# sch.net
KiCad netlist of a schematic drawn in Altium Designer
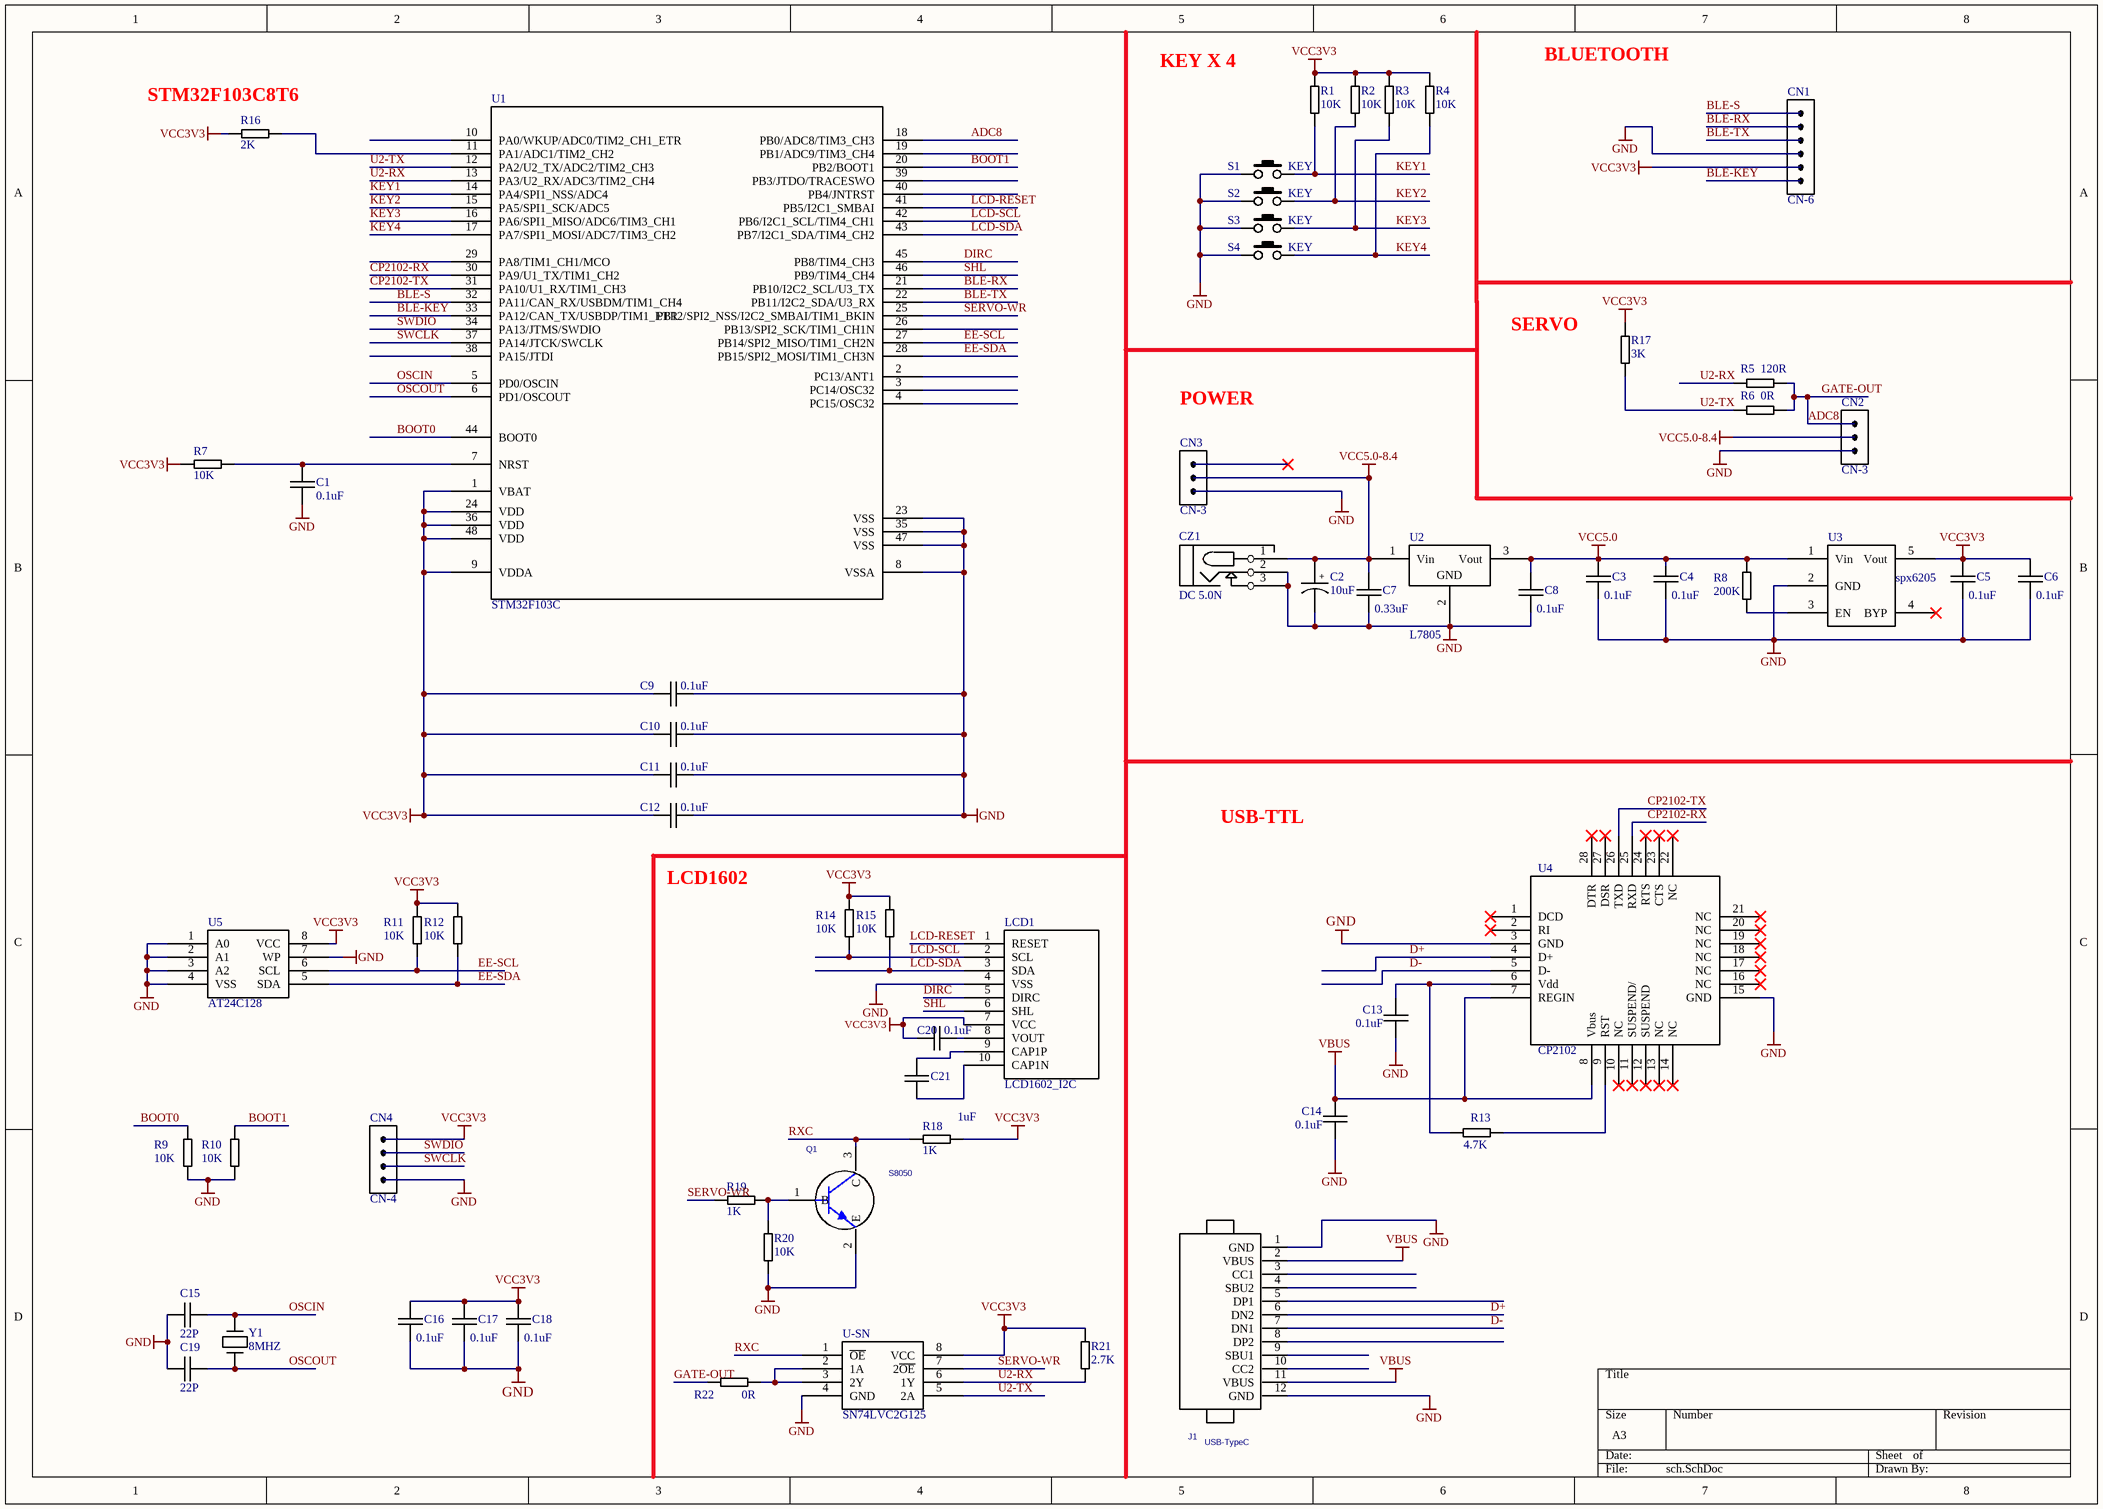
[diagram p0: sch.SchDoc]

(export (version "E")
  (design (tool "Eeschema 10.0.6"))
  (components
    (comp (ref "C1")
      (value "0.1uF")
      (footprint "CAP-0603")
      (description "Capacitor")
      (libsource (lib "综合元件") (part "CAP"))
    )
    (comp (ref "C2")
      (value "10uF")
      (footprint "CAP-A")
      (description "Polar Capacitor")
      (libsource (lib "1-Components") (part "CAP(POL)"))
    )
    (comp (ref "C3")
      (value "0.1uF")
      (footprint "CAP-0603")
      (description "Capacitor")
      (libsource (lib "综合元件") (part "CAP"))
    )
    (comp (ref "C4")
      (value "0.1uF")
      (footprint "CAP-0603")
      (description "Capacitor")
      (libsource (lib "综合元件") (part "CAP"))
    )
    (comp (ref "C5")
      (value "0.1uF")
      (footprint "CAP-0603")
      (description "Capacitor")
      (libsource (lib "综合元件") (part "CAP"))
    )
    (comp (ref "C6")
      (value "0.1uF")
      (footprint "CAP-0603")
      (description "Capacitor")
      (libsource (lib "综合元件") (part "CAP"))
    )
    (comp (ref "C7")
      (value "0.33uF")
      (footprint "CAP-0603")
      (description "Capacitor")
      (libsource (lib "综合元件") (part "CAP"))
    )
    (comp (ref "C8")
      (value "0.1uF")
      (footprint "CAP-0603")
      (description "Capacitor")
      (libsource (lib "综合元件") (part "CAP"))
    )
    (comp (ref "C9")
      (value "0.1uF")
      (footprint "CAP-0603")
      (description "Capacitor")
      (libsource (lib "综合元件") (part "CAP"))
    )
    (comp (ref "C10")
      (value "0.1uF")
      (footprint "CAP-0603")
      (description "Capacitor")
      (libsource (lib "综合元件") (part "CAP"))
    )
    (comp (ref "C11")
      (value "0.1uF")
      (footprint "CAP-0603")
      (description "Capacitor")
      (libsource (lib "综合元件") (part "CAP"))
    )
    (comp (ref "C12")
      (value "0.1uF")
      (footprint "CAP-0603")
      (description "Capacitor")
      (libsource (lib "综合元件") (part "CAP"))
    )
    (comp (ref "C13")
      (value "0.1uF")
      (footprint "CAP-0603")
      (description "Capacitor")
      (libsource (lib "综合元件") (part "CAP"))
    )
    (comp (ref "C14")
      (value "0.1uF")
      (footprint "CAP-0603")
      (description "Capacitor")
      (libsource (lib "综合元件") (part "CAP"))
    )
    (comp (ref "C15")
      (value "22P")
      (footprint "CAP-0603")
      (description "Capacitor")
      (libsource (lib "1-Components") (part "CAP"))
    )
    (comp (ref "C16")
      (value "0.1uF")
      (footprint "CAP-0603")
      (description "Capacitor")
      (libsource (lib "综合元件") (part "CAP"))
    )
    (comp (ref "C17")
      (value "0.1uF")
      (footprint "CAP-0603")
      (description "Capacitor")
      (libsource (lib "综合元件") (part "CAP"))
    )
    (comp (ref "C18")
      (value "0.1uF")
      (footprint "CAP-0603")
      (description "Capacitor")
      (libsource (lib "综合元件") (part "CAP"))
    )
    (comp (ref "C19")
      (value "22P")
      (footprint "CAP-0603")
      (description "Capacitor")
      (libsource (lib "1-Components") (part "CAP"))
    )
    (comp (ref "C20")
      (value "0.1uF")
      (footprint "CAP-0603")
      (description "Capacitor")
      (libsource (lib "综合元件") (part "CAP"))
    )
    (comp (ref "C21")
      (value "1uF")
      (footprint "CAP-0603")
      (description "Capacitor")
      (libsource (lib "综合元件") (part "CAP"))
    )
    (comp (ref "CN1") (value "CN-6") (footprint "CN-6") (libsource (lib "2-Connectors") (part "CN-6")))
    (comp (ref "CN2") (value "CN-3") (footprint "IDC-3×1") (libsource (lib "2-Connectors") (part "CN-3")))
    (comp (ref "CN3") (value "CN-3") (footprint "IDC-3×1") (libsource (lib "2-Connectors") (part "CN-3")))
    (comp (ref "CN4") (value "CN-4") (footprint "IDC-4×1") (libsource (lib "2-Connectors") (part "CN-4")))
    (comp (ref "CZ1")
      (value "DC 5.0N")
      (footprint "DC-005(N)")
      (libsource (lib "2-Connectors") (part "DC 5.0N"))
    )
    (comp (ref "J1")
      (value "USB-TypeC")
      (footprint "USB-TYPEC")
      (libsource (lib "2-Connectors") (part "USB-TypeC"))
    )
    (comp (ref "LCD1")
      (value "LCD1602_I2C")
      (footprint "LCD-IIC")
      (description "LCD1602")
      (libsource (lib "6-Modulars") (part "LCD1602_I2C"))
    )
    (comp (ref "Q1")
      (value "S8050")
      (footprint "SOT-23(3)")
      (description "NPN")
      (libsource (lib "3-ICs Normal") (part "S8050"))
    )
    (comp (ref "R1")
      (value "10K")
      (footprint "RES-0603")
      (description "Resistor")
      (libsource (lib "1-Components") (part "RES"))
    )
    (comp (ref "R2")
      (value "10K")
      (footprint "RES-0603")
      (description "Resistor")
      (libsource (lib "1-Components") (part "RES"))
    )
    (comp (ref "R3")
      (value "10K")
      (footprint "RES-0603")
      (description "Resistor")
      (libsource (lib "1-Components") (part "RES"))
    )
    (comp (ref "R4")
      (value "10K")
      (footprint "RES-0603")
      (description "Resistor")
      (libsource (lib "1-Components") (part "RES"))
    )
    (comp (ref "R5")
      (value "120R")
      (footprint "RES-0603")
      (description "Resistor")
      (libsource (lib "1-Components") (part "RES"))
    )
    (comp (ref "R6")
      (value "0R")
      (footprint "RES-0603")
      (description "Resistor")
      (libsource (lib "1-Components") (part "RES"))
    )
    (comp (ref "R7")
      (value "10K")
      (footprint "RES-0603")
      (description "Resistor")
      (libsource (lib "综合元件") (part "RES"))
    )
    (comp (ref "R8")
      (value "200K")
      (footprint "RES-0603")
      (description "Resistor")
      (libsource (lib "1-Components") (part "RES"))
    )
    (comp (ref "R9")
      (value "10K")
      (footprint "RES-0603")
      (description "Resistor")
      (libsource (lib "1-Components") (part "RES"))
    )
    (comp (ref "R10")
      (value "10K")
      (footprint "RES-0603")
      (description "Resistor")
      (libsource (lib "1-Components") (part "RES"))
    )
    (comp (ref "R11")
      (value "10K")
      (footprint "RES-0603")
      (description "Resistor")
      (libsource (lib "1-Components") (part "RES"))
    )
    (comp (ref "R12")
      (value "10K")
      (footprint "RES-0603")
      (description "Resistor")
      (libsource (lib "1-Components") (part "RES"))
    )
    (comp (ref "R13")
      (value "4.7K")
      (footprint "RES-0603")
      (description "Resistor")
      (libsource (lib "1-Components") (part "RES"))
    )
    (comp (ref "R14")
      (value "10K")
      (footprint "RES-0603")
      (description "Resistor")
      (libsource (lib "1-Components") (part "RES"))
    )
    (comp (ref "R15")
      (value "10K")
      (footprint "RES-0603")
      (description "Resistor")
      (libsource (lib "1-Components") (part "RES"))
    )
    (comp (ref "R16")
      (value "2K")
      (footprint "RES-0603")
      (description "Resistor")
      (libsource (lib "1-Components") (part "RES"))
    )
    (comp (ref "R17")
      (value "3K")
      (footprint "RES-0603")
      (description "Resistor")
      (libsource (lib "1-Components") (part "RES"))
    )
    (comp (ref "R18")
      (value "1K")
      (footprint "RES-0603")
      (description "Resistor")
      (libsource (lib "1-Components") (part "RES"))
    )
    (comp (ref "R19")
      (value "1K")
      (footprint "RES-0603")
      (description "Resistor")
      (libsource (lib "1-Components") (part "RES"))
    )
    (comp (ref "R20")
      (value "10K")
      (footprint "RES-0603")
      (description "Resistor")
      (libsource (lib "1-Components") (part "RES"))
    )
    (comp (ref "R21")
      (value "2.7K")
      (footprint "RES-0603")
      (description "Resistor")
      (libsource (lib "1-Components") (part "RES"))
    )
    (comp (ref "R22")
      (value "0R")
      (footprint "RES-0603")
      (description "Resistor")
      (libsource (lib "1-Components") (part "RES"))
    )
    (comp (ref "S1") (value "KEY") (footprint "KEY-4X4X1.5") (libsource (lib "2-Connectors") (part "KEY")))
    (comp (ref "S2") (value "KEY") (footprint "KEY-4X4X1.5") (libsource (lib "2-Connectors") (part "KEY")))
    (comp (ref "S3") (value "KEY") (footprint "KEY-4X4X1.5") (libsource (lib "2-Connectors") (part "KEY")))
    (comp (ref "S4") (value "KEY") (footprint "KEY-4X4X1.5") (libsource (lib "2-Connectors") (part "KEY")))
    (comp (ref "U-SN")
      (value "SN74LVC2G125")
      (footprint "SOP-8(SN74)")
      (libsource (lib "3-ICs Normal") (part "SN74LVC2G125"))
    )
    (comp (ref "U1")
      (value "STM32F103C")
      (footprint "LQFP-48")
      (fields (field (name "PUBLISHER") "Altium Limited"))
      (libsource (lib "5-ICs Mcu") (part "STM32F103C(LQFP)"))
    )
    (comp (ref "U2") (value "L7805") (footprint "TO-252") (libsource (lib "3-ICs Normal") (part "78XX")))
    (comp (ref "U3")
      (value "spx6205")
      (footprint "SOT-23(5)")
      (libsource (lib "3-ICs Normal") (part "SP6205(FIXED)"))
    )
    (comp (ref "U4") (value "CP2102") (footprint "QFN-28") (libsource (lib "5-ICs Mcu") (part "MPU6050_1")))
    (comp (ref "U5")
      (value "AT24C128")
      (footprint "SOP-8(3.9)")
      (libsource (lib "3-ICs Normal") (part "AT24C128"))
    )
    (comp (ref "Y1")
      (value "8MHZ")
      (footprint "XTAL-2512")
      (description "Crystal")
      (libsource (lib "1-Components") (part "XTAL(1)"))
    )
  )
  (nets
    (net (code "1") (name "/ADC8") (class "Default")
      (node (ref "CN2") (pin "1") (pinfunction "1_1") (pintype "passive"))
      (node (ref "R22") (pin "2") (pinfunction "2_2") (pintype "passive"))
      (node (ref "R5") (pin "2") (pinfunction "2_2") (pintype "passive"))
      (node (ref "R6") (pin "2") (pinfunction "2_2") (pintype "passive"))
      (node (ref "U1") (pin "18") (pinfunction "PB0/ADC8/TIM3_CH3_18") (pintype "passive"))
    )
    (net (code "2") (name "/BLE-KEY") (class "Default")
      (node (ref "CN1") (pin "6") (pinfunction "6_6") (pintype "passive"))
      (node (ref "U1") (pin "33") (pinfunction "PA12/CAN_TX/USBDP/TIM1_ETR_33") (pintype "passive"))
    )
    (net (code "3") (name "/BLE-RX") (class "Default")
      (node (ref "CN1") (pin "2") (pinfunction "2_2") (pintype "passive"))
      (node (ref "U1") (pin "21") (pinfunction "PB10/I2C2_SCL/U3_TX_21") (pintype "passive"))
    )
    (net (code "4") (name "/BLE-S") (class "Default")
      (node (ref "CN1") (pin "1") (pinfunction "1_1") (pintype "passive"))
      (node (ref "U1") (pin "32") (pinfunction "PA11/CAN_RX/USBDM/TIM1_CH4_32") (pintype "passive"))
    )
    (net (code "5") (name "/BLE-TX") (class "Default")
      (node (ref "CN1") (pin "3") (pinfunction "3_3") (pintype "passive"))
      (node (ref "U1") (pin "22") (pinfunction "PB11/I2C2_SDA/U3_RX_22") (pintype "passive"))
    )
    (net (code "6") (name "/BOOT0") (class "Default")
      (node (ref "R9") (pin "1") (pinfunction "1_1") (pintype "passive"))
      (node (ref "U1") (pin "44") (pinfunction "BOOT0_44") (pintype "passive"))
    )
    (net (code "7") (name "/BOOT1") (class "Default")
      (node (ref "R10") (pin "1") (pinfunction "1_1") (pintype "passive"))
      (node (ref "U1") (pin "20") (pinfunction "PB2/BOOT1_20") (pintype "passive"))
    )
    (net (code "8") (name "/CP2102-RX") (class "Default")
      (node (ref "U1") (pin "30") (pinfunction "PA9/U1_TX/TIM1_CH2_30") (pintype "passive"))
      (node (ref "U4") (pin "25") (pinfunction "RXD_25") (pintype "passive"))
    )
    (net (code "9") (name "/CP2102-TX") (class "Default")
      (node (ref "U1") (pin "31") (pinfunction "PA10/U1_RX/TIM1_CH3_31") (pintype "passive"))
      (node (ref "U4") (pin "26") (pinfunction "TXD_26") (pintype "passive"))
    )
    (net (code "10") (name "/D+") (class "Default")
      (node (ref "J1") (pin "6") (pinfunction "DN2_6") (pintype "passive"))
      (node (ref "U4") (pin "4") (pinfunction "D+_4") (pintype "passive"))
    )
    (net (code "11") (name "/D-") (class "Default")
      (node (ref "J1") (pin "7") (pinfunction "DN1_7") (pintype "passive"))
      (node (ref "U4") (pin "5") (pinfunction "D-_5") (pintype "passive"))
    )
    (net (code "12") (name "/DIRC") (class "Default")
      (node (ref "LCD1") (pin "5") (pinfunction "DIRC_5") (pintype "passive"))
      (node (ref "U1") (pin "45") (pinfunction "PB8/TIM4_CH3_45") (pintype "passive"))
    )
    (net (code "13") (name "/EE-SCL") (class "Default")
      (node (ref "R11") (pin "2") (pinfunction "2_2") (pintype "passive"))
      (node (ref "U1") (pin "27") (pinfunction "PB14/SPI2_MISO/TIM1_CH2N_27") (pintype "passive"))
      (node (ref "U5") (pin "6") (pinfunction "SCL_6") (pintype "passive"))
    )
    (net (code "14") (name "/EE-SDA") (class "Default")
      (node (ref "R12") (pin "2") (pinfunction "2_2") (pintype "passive"))
      (node (ref "U1") (pin "28") (pinfunction "PB15/SPI2_MOSI/TIM1_CH3N_28") (pintype "passive"))
      (node (ref "U5") (pin "5") (pinfunction "SDA_5") (pintype "passive"))
    )
    (net (code "15") (name "/KEY1") (class "Default")
      (node (ref "R1") (pin "1") (pinfunction "1_1") (pintype "passive"))
      (node (ref "S1") (pin "2") (pinfunction "2_2") (pintype "passive"))
      (node (ref "U1") (pin "14") (pinfunction "PA4/SPI1_NSS/ADC4_14") (pintype "passive"))
    )
    (net (code "16") (name "/KEY2") (class "Default")
      (node (ref "R2") (pin "1") (pinfunction "1_1") (pintype "passive"))
      (node (ref "S2") (pin "2") (pinfunction "2_2") (pintype "passive"))
      (node (ref "U1") (pin "15") (pinfunction "PA5/SPI1_SCK/ADC5_15") (pintype "passive"))
    )
    (net (code "17") (name "/KEY3") (class "Default")
      (node (ref "R3") (pin "1") (pinfunction "1_1") (pintype "passive"))
      (node (ref "S3") (pin "2") (pinfunction "2_2") (pintype "passive"))
      (node (ref "U1") (pin "16") (pinfunction "PA6/SPI1_MISO/ADC6/TIM3_CH1_16") (pintype "passive"))
    )
    (net (code "18") (name "/KEY4") (class "Default")
      (node (ref "R4") (pin "1") (pinfunction "1_1") (pintype "passive"))
      (node (ref "S4") (pin "2") (pinfunction "2_2") (pintype "passive"))
      (node (ref "U1") (pin "17") (pinfunction "PA7/SPI1_MOSI/ADC7/TIM3_CH2_17") (pintype "passive"))
    )
    (net (code "19") (name "/LCD-RESET") (class "Default")
      (node (ref "LCD1") (pin "1") (pinfunction "RESET_1") (pintype "passive"))
      (node (ref "U1") (pin "41") (pinfunction "PB5/I2C1_SMBAI_41") (pintype "passive"))
    )
    (net (code "20") (name "/LCD-SCL") (class "Default")
      (node (ref "LCD1") (pin "2") (pinfunction "SCL_2") (pintype "passive"))
      (node (ref "R14") (pin "2") (pinfunction "2_2") (pintype "passive"))
      (node (ref "U1") (pin "42") (pinfunction "PB6/I2C1_SCL/TIM4_CH1_42") (pintype "passive"))
    )
    (net (code "21") (name "/LCD-SDA") (class "Default")
      (node (ref "LCD1") (pin "3") (pinfunction "SDA_3") (pintype "passive"))
      (node (ref "R15") (pin "2") (pinfunction "2_2") (pintype "passive"))
      (node (ref "U1") (pin "43") (pinfunction "PB7/I2C1_SDA/TIM4_CH2_43") (pintype "passive"))
    )
    (net (code "22") (name "/OSCIN") (class "Default")
      (node (ref "C15") (pin "2") (pinfunction "2_2") (pintype "passive"))
      (node (ref "U1") (pin "5") (pinfunction "PD0/OSCIN_5") (pintype "passive"))
      (node (ref "Y1") (pin "2") (pinfunction "2_2") (pintype "passive"))
    )
    (net (code "23") (name "/OSCOUT") (class "Default")
      (node (ref "C19") (pin "2") (pinfunction "2_2") (pintype "passive"))
      (node (ref "U1") (pin "6") (pinfunction "PD1/OSCOUT_6") (pintype "passive"))
      (node (ref "Y1") (pin "1") (pinfunction "1_1") (pintype "passive"))
    )
    (net (code "24") (name "/RXC") (class "Default")
      (node (ref "Q1") (pin "3") (pinfunction "C_3") (pintype "passive"))
      (node (ref "R18") (pin "1") (pinfunction "1_1") (pintype "passive"))
      (node (ref "U-SN") (pin "1") (pinfunction "~{OE}_1") (pintype "passive"))
    )
    (net (code "25") (name "/SERVO-WR") (class "Default")
      (node (ref "R19") (pin "1") (pinfunction "1_1") (pintype "passive"))
      (node (ref "U-SN") (pin "7") (pinfunction "2~{OE}_7") (pintype "passive"))
      (node (ref "U1") (pin "25") (pinfunction "PB12/SPI2_NSS/I2C2_SMBAI/TIM1_BKIN_25") (pintype "passive"))
    )
    (net (code "26") (name "/SHL") (class "Default")
      (node (ref "LCD1") (pin "6") (pinfunction "SHL_6") (pintype "passive"))
      (node (ref "U1") (pin "46") (pinfunction "PB9/TIM4_CH4_46") (pintype "passive"))
    )
    (net (code "27") (name "/SWCLK") (class "Default")
      (node (ref "CN4") (pin "3") (pinfunction "3_3") (pintype "passive"))
      (node (ref "U1") (pin "37") (pinfunction "PA14/JTCK/SWCLK_37") (pintype "passive"))
    )
    (net (code "28") (name "/SWDIO") (class "Default")
      (node (ref "CN4") (pin "2") (pinfunction "2_2") (pintype "passive"))
      (node (ref "U1") (pin "34") (pinfunction "PA13/JTMS/SWDIO_34") (pintype "passive"))
    )
    (net (code "29") (name "/U2-RX") (class "Default")
      (node (ref "R21") (pin "1") (pinfunction "1_1") (pintype "passive"))
      (node (ref "R5") (pin "1") (pinfunction "1_1") (pintype "passive"))
      (node (ref "U-SN") (pin "6") (pinfunction "1Y_6") (pintype "passive"))
      (node (ref "U1") (pin "13") (pinfunction "PA3/U2_RX/ADC3/TIM2_CH4_13") (pintype "passive"))
    )
    (net (code "30") (name "/U2-TX") (class "Default")
      (node (ref "R17") (pin "1") (pinfunction "1_1") (pintype "passive"))
      (node (ref "R6") (pin "1") (pinfunction "1_1") (pintype "passive"))
      (node (ref "U-SN") (pin "5") (pinfunction "2A_5") (pintype "passive"))
      (node (ref "U1") (pin "12") (pinfunction "PA2/U2_TX/ADC2/TIM2_CH3_12") (pintype "passive"))
    )
    (net (code "31") (name "GND") (class "Default")
      (node (ref "C1") (pin "2") (pinfunction "2_2") (pintype "passive"))
      (node (ref "C10") (pin "1") (pinfunction "1_1") (pintype "passive"))
      (node (ref "C11") (pin "1") (pinfunction "1_1") (pintype "passive"))
      (node (ref "C12") (pin "1") (pinfunction "1_1") (pintype "passive"))
      (node (ref "C13") (pin "2") (pinfunction "2_2") (pintype "passive"))
      (node (ref "C14") (pin "2") (pinfunction "2_2") (pintype "passive"))
      (node (ref "C15") (pin "1") (pinfunction "1_1") (pintype "passive"))
      (node (ref "C16") (pin "2") (pinfunction "2_2") (pintype "passive"))
      (node (ref "C17") (pin "2") (pinfunction "2_2") (pintype "passive"))
      (node (ref "C18") (pin "2") (pinfunction "2_2") (pintype "passive"))
      (node (ref "C19") (pin "1") (pinfunction "1_1") (pintype "passive"))
      (node (ref "C2") (pin "2") (pinfunction "2_2") (pintype "passive"))
      (node (ref "C3") (pin "2") (pinfunction "2_2") (pintype "passive"))
      (node (ref "C4") (pin "2") (pinfunction "2_2") (pintype "passive"))
      (node (ref "C5") (pin "2") (pinfunction "2_2") (pintype "passive"))
      (node (ref "C6") (pin "2") (pinfunction "2_2") (pintype "passive"))
      (node (ref "C7") (pin "2") (pinfunction "2_2") (pintype "passive"))
      (node (ref "C8") (pin "2") (pinfunction "2_2") (pintype "passive"))
      (node (ref "C9") (pin "1") (pinfunction "1_1") (pintype "passive"))
      (node (ref "CN1") (pin "4") (pinfunction "4_4") (pintype "passive"))
      (node (ref "CN2") (pin "3") (pinfunction "3_3") (pintype "passive"))
      (node (ref "CN3") (pin "3") (pinfunction "3_3") (pintype "passive"))
      (node (ref "CN4") (pin "4") (pinfunction "4_4") (pintype "passive"))
      (node (ref "CZ1") (pin "2") (pinfunction "A_2") (pintype "passive"))
      (node (ref "CZ1") (pin "3") (pinfunction "B_3") (pintype "passive"))
      (node (ref "J1") (pin "1") (pinfunction "GND_1") (pintype "passive"))
      (node (ref "J1") (pin "12") (pinfunction "GND_12") (pintype "passive"))
      (node (ref "LCD1") (pin "4") (pinfunction "VSS_4") (pintype "passive"))
      (node (ref "Q1") (pin "2") (pinfunction "E_2") (pintype "passive"))
      (node (ref "R10") (pin "2") (pinfunction "2_2") (pintype "passive"))
      (node (ref "R20") (pin "2") (pinfunction "2_2") (pintype "passive"))
      (node (ref "R9") (pin "2") (pinfunction "2_2") (pintype "passive"))
      (node (ref "S1") (pin "1") (pinfunction "1_1") (pintype "passive"))
      (node (ref "S2") (pin "1") (pinfunction "1_1") (pintype "passive"))
      (node (ref "S3") (pin "1") (pinfunction "1_1") (pintype "passive"))
      (node (ref "S4") (pin "1") (pinfunction "1_1") (pintype "passive"))
      (node (ref "U-SN") (pin "4") (pinfunction "GND_4") (pintype "passive"))
      (node (ref "U1") (pin "23") (pinfunction "VSS_23") (pintype "passive"))
      (node (ref "U1") (pin "35") (pinfunction "VSS_35") (pintype "passive"))
      (node (ref "U1") (pin "47") (pinfunction "VSS_47") (pintype "passive"))
      (node (ref "U1") (pin "8") (pinfunction "VSSA_8") (pintype "passive"))
      (node (ref "U2") (pin "2") (pinfunction "GND_2") (pintype "passive"))
      (node (ref "U3") (pin "2") (pinfunction "GND_2") (pintype "passive"))
      (node (ref "U4") (pin "15") (pinfunction "GND_15") (pintype "passive"))
      (node (ref "U4") (pin "3") (pinfunction "GND_3") (pintype "passive"))
      (node (ref "U5") (pin "1") (pinfunction "A0_1") (pintype "passive"))
      (node (ref "U5") (pin "2") (pinfunction "A1_2") (pintype "passive"))
      (node (ref "U5") (pin "3") (pinfunction "A2_3") (pintype "passive"))
      (node (ref "U5") (pin "4") (pinfunction "VSS_4") (pintype "passive"))
      (node (ref "U5") (pin "7") (pinfunction "WP_7") (pintype "passive"))
    )
    (net (code "32") (name "Net-(LCD1-CAP1N)") (class "Default")
      (node (ref "C21") (pin "2") (pinfunction "2_2") (pintype "passive"))
      (node (ref "LCD1") (pin "10") (pinfunction "CAP1N_10") (pintype "passive"))
    )
    (net (code "33") (name "Net-(LCD1-CAP1P)") (class "Default")
      (node (ref "C21") (pin "1") (pinfunction "1_1") (pintype "passive"))
      (node (ref "LCD1") (pin "9") (pinfunction "CAP1P_9") (pintype "passive"))
    )
    (net (code "34") (name "Net-(LCD1-VOUT)") (class "Default")
      (node (ref "C20") (pin "2") (pinfunction "2_2") (pintype "passive"))
      (node (ref "LCD1") (pin "8") (pinfunction "VOUT_8") (pintype "passive"))
    )
    (net (code "35") (name "Net-(Q1-B)") (class "Default")
      (node (ref "Q1") (pin "1") (pinfunction "B_1") (pintype "passive"))
      (node (ref "R19") (pin "2") (pinfunction "2_2") (pintype "passive"))
      (node (ref "R20") (pin "1") (pinfunction "1_1") (pintype "passive"))
    )
    (net (code "36") (name "Net-(U-SN-1A)") (class "Default")
      (node (ref "R22") (pin "1") (pinfunction "1_1") (pintype "passive"))
      (node (ref "U-SN") (pin "2") (pinfunction "1A_2") (pintype "passive"))
      (node (ref "U-SN") (pin "3") (pinfunction "2Y_3") (pintype "passive"))
    )
    (net (code "37") (name "Net-(U1-NRST)") (class "Default")
      (node (ref "C1") (pin "1") (pinfunction "1_1") (pintype "passive"))
      (node (ref "R7") (pin "2") (pinfunction "2_2") (pintype "passive"))
      (node (ref "U1") (pin "7") (pinfunction "NRST_7") (pintype "passive"))
    )
    (net (code "38") (name "Net-(U1-PA1{slash}ADC1{slash}TIM2_CH2)") (class "Default")
      (node (ref "R16") (pin "1") (pinfunction "1_1") (pintype "passive"))
      (node (ref "U1") (pin "11") (pinfunction "PA1/ADC1/TIM2_CH2_11") (pintype "passive"))
    )
    (net (code "39") (name "Net-(U3-EN)") (class "Default")
      (node (ref "R8") (pin "2") (pinfunction "2_2") (pintype "passive"))
      (node (ref "U3") (pin "3") (pinfunction "EN_3") (pintype "passive"))
    )
    (net (code "40") (name "Net-(U4-RST)") (class "Default")
      (node (ref "R13") (pin "2") (pinfunction "2_2") (pintype "passive"))
      (node (ref "U4") (pin "9") (pinfunction "RST_9") (pintype "passive"))
    )
    (net (code "41") (name "Net-(U4-Vdd)") (class "Default")
      (node (ref "C13") (pin "1") (pinfunction "1_1") (pintype "passive"))
      (node (ref "R13") (pin "1") (pinfunction "1_1") (pintype "passive"))
      (node (ref "U4") (pin "6") (pinfunction "Vdd_6") (pintype "passive"))
    )
    (net (code "42") (name "VBUS") (class "Default")
      (node (ref "C14") (pin "1") (pinfunction "1_1") (pintype "passive"))
      (node (ref "J1") (pin "11") (pinfunction "VBUS_11") (pintype "passive"))
      (node (ref "J1") (pin "2") (pinfunction "VBUS_2") (pintype "passive"))
      (node (ref "U4") (pin "7") (pinfunction "REGIN_7") (pintype "passive"))
      (node (ref "U4") (pin "8") (pinfunction "Vbus_8") (pintype "passive"))
    )
    (net (code "43") (name "VCC3V3") (class "Default")
      (node (ref "C10") (pin "2") (pinfunction "2_2") (pintype "passive"))
      (node (ref "C11") (pin "2") (pinfunction "2_2") (pintype "passive"))
      (node (ref "C12") (pin "2") (pinfunction "2_2") (pintype "passive"))
      (node (ref "C16") (pin "1") (pinfunction "1_1") (pintype "passive"))
      (node (ref "C17") (pin "1") (pinfunction "1_1") (pintype "passive"))
      (node (ref "C18") (pin "1") (pinfunction "1_1") (pintype "passive"))
      (node (ref "C20") (pin "1") (pinfunction "1_1") (pintype "passive"))
      (node (ref "C5") (pin "1") (pinfunction "1_1") (pintype "passive"))
      (node (ref "C6") (pin "1") (pinfunction "1_1") (pintype "passive"))
      (node (ref "C9") (pin "2") (pinfunction "2_2") (pintype "passive"))
      (node (ref "CN1") (pin "5") (pinfunction "5_5") (pintype "passive"))
      (node (ref "CN4") (pin "1") (pinfunction "1_1") (pintype "passive"))
      (node (ref "LCD1") (pin "7") (pinfunction "VCC_7") (pintype "passive"))
      (node (ref "R1") (pin "2") (pinfunction "2_2") (pintype "passive"))
      (node (ref "R11") (pin "1") (pinfunction "1_1") (pintype "passive"))
      (node (ref "R12") (pin "1") (pinfunction "1_1") (pintype "passive"))
      (node (ref "R14") (pin "1") (pinfunction "1_1") (pintype "passive"))
      (node (ref "R15") (pin "1") (pinfunction "1_1") (pintype "passive"))
      (node (ref "R16") (pin "2") (pinfunction "2_2") (pintype "passive"))
      (node (ref "R17") (pin "2") (pinfunction "2_2") (pintype "passive"))
      (node (ref "R18") (pin "2") (pinfunction "2_2") (pintype "passive"))
      (node (ref "R2") (pin "2") (pinfunction "2_2") (pintype "passive"))
      (node (ref "R21") (pin "2") (pinfunction "2_2") (pintype "passive"))
      (node (ref "R3") (pin "2") (pinfunction "2_2") (pintype "passive"))
      (node (ref "R4") (pin "2") (pinfunction "2_2") (pintype "passive"))
      (node (ref "R7") (pin "1") (pinfunction "1_1") (pintype "passive"))
      (node (ref "U-SN") (pin "8") (pinfunction "VCC_8") (pintype "passive"))
      (node (ref "U1") (pin "1") (pinfunction "VBAT_1") (pintype "passive"))
      (node (ref "U1") (pin "24") (pinfunction "VDD_24") (pintype "passive"))
      (node (ref "U1") (pin "36") (pinfunction "VDD_36") (pintype "passive"))
      (node (ref "U1") (pin "48") (pinfunction "VDD_48") (pintype "passive"))
      (node (ref "U1") (pin "9") (pinfunction "VDDA_9") (pintype "passive"))
      (node (ref "U3") (pin "5") (pinfunction "Vout_5") (pintype "passive"))
      (node (ref "U5") (pin "8") (pinfunction "VCC_8") (pintype "passive"))
    )
    (net (code "44") (name "VCC5.0") (class "Default")
      (node (ref "C3") (pin "1") (pinfunction "1_1") (pintype "passive"))
      (node (ref "C4") (pin "1") (pinfunction "1_1") (pintype "passive"))
      (node (ref "C8") (pin "1") (pinfunction "1_1") (pintype "passive"))
      (node (ref "R8") (pin "1") (pinfunction "1_1") (pintype "passive"))
      (node (ref "U2") (pin "3") (pinfunction "Vout_3") (pintype "passive"))
      (node (ref "U3") (pin "1") (pinfunction "Vin_1") (pintype "passive"))
    )
    (net (code "45") (name "VCC5.0-8.4") (class "Default")
      (node (ref "C2") (pin "1") (pinfunction "1_1") (pintype "passive"))
      (node (ref "C7") (pin "1") (pinfunction "1_1") (pintype "passive"))
      (node (ref "CN2") (pin "2") (pinfunction "2_2") (pintype "passive"))
      (node (ref "CN3") (pin "2") (pinfunction "2_2") (pintype "passive"))
      (node (ref "CZ1") (pin "1") (pinfunction "+_1") (pintype "passive"))
      (node (ref "U2") (pin "1") (pinfunction "Vin_1") (pintype "passive"))
    )
    (net (code "46") (name "unconnected-(CN3-Pad1)") (class "Default")
      (node (ref "CN3") (pin "1") (pinfunction "1_1") (pintype "passive+no_connect"))
    )
    (net (code "47") (name "unconnected-(J1-CC1-Pad3)") (class "Default")
      (node (ref "J1") (pin "3") (pinfunction "CC1_3") (pintype "passive"))
    )
    (net (code "48") (name "unconnected-(J1-CC2-Pad10)") (class "Default")
      (node (ref "J1") (pin "10") (pinfunction "CC2_10") (pintype "passive"))
    )
    (net (code "49") (name "unconnected-(J1-DP1-Pad5)") (class "Default")
      (node (ref "J1") (pin "5") (pinfunction "DP1_5") (pintype "passive"))
    )
    (net (code "50") (name "unconnected-(J1-DP2-Pad8)") (class "Default")
      (node (ref "J1") (pin "8") (pinfunction "DP2_8") (pintype "passive"))
    )
    (net (code "51") (name "unconnected-(J1-SBU1-Pad9)") (class "Default")
      (node (ref "J1") (pin "9") (pinfunction "SBU1_9") (pintype "passive"))
    )
    (net (code "52") (name "unconnected-(J1-SBU2-Pad4)") (class "Default")
      (node (ref "J1") (pin "4") (pinfunction "SBU2_4") (pintype "passive"))
    )
    (net (code "53") (name "unconnected-(U1-PA0{slash}WKUP{slash}ADC0{slash}TIM2_CH1_ETR-Pad10)") (class "Default")
      (node (ref "U1") (pin "10") (pinfunction "PA0/WKUP/ADC0/TIM2_CH1_ETR_10") (pintype "passive"))
    )
    (net (code "54") (name "unconnected-(U1-PA8{slash}TIM1_CH1{slash}MCO-Pad29)") (class "Default")
      (node (ref "U1") (pin "29") (pinfunction "PA8/TIM1_CH1/MCO_29") (pintype "passive"))
    )
    (net (code "55") (name "unconnected-(U1-PA15{slash}JTDI-Pad38)") (class "Default")
      (node (ref "U1") (pin "38") (pinfunction "PA15/JTDI_38") (pintype "passive"))
    )
    (net (code "56") (name "unconnected-(U1-PB1{slash}ADC9{slash}TIM3_CH4-Pad19)") (class "Default")
      (node (ref "U1") (pin "19") (pinfunction "PB1/ADC9/TIM3_CH4_19") (pintype "passive"))
    )
    (net (code "57") (name "unconnected-(U1-PB3{slash}JTDO{slash}TRACESWO-Pad39)") (class "Default")
      (node (ref "U1") (pin "39") (pinfunction "PB3/JTDO/TRACESWO_39") (pintype "passive"))
    )
    (net (code "58") (name "unconnected-(U1-PB4{slash}JNTRST-Pad40)") (class "Default")
      (node (ref "U1") (pin "40") (pinfunction "PB4/JNTRST_40") (pintype "passive"))
    )
    (net (code "59") (name "unconnected-(U1-PB13{slash}SPI2_SCK{slash}TIM1_CH1N-Pad26)") (class "Default")
      (node (ref "U1") (pin "26") (pinfunction "PB13/SPI2_SCK/TIM1_CH1N_26") (pintype "passive"))
    )
    (net (code "60") (name "unconnected-(U1-PC13{slash}ANT1-Pad2)") (class "Default")
      (node (ref "U1") (pin "2") (pinfunction "PC13/ANT1_2") (pintype "passive"))
    )
    (net (code "61") (name "unconnected-(U1-PC14{slash}OSC32-Pad3)") (class "Default")
      (node (ref "U1") (pin "3") (pinfunction "PC14/OSC32_3") (pintype "passive"))
    )
    (net (code "62") (name "unconnected-(U1-PC15{slash}OSC32-Pad4)") (class "Default")
      (node (ref "U1") (pin "4") (pinfunction "PC15/OSC32_4") (pintype "passive"))
    )
    (net (code "63") (name "unconnected-(U3-BYP-Pad4)") (class "Default")
      (node (ref "U3") (pin "4") (pinfunction "BYP_4") (pintype "passive+no_connect"))
    )
    (net (code "64") (name "unconnected-(U4-CTS-Pad23)") (class "Default")
      (node (ref "U4") (pin "23") (pinfunction "CTS_23") (pintype "passive+no_connect"))
    )
    (net (code "65") (name "unconnected-(U4-DCD-Pad1)") (class "Default")
      (node (ref "U4") (pin "1") (pinfunction "DCD_1") (pintype "passive+no_connect"))
    )
    (net (code "66") (name "unconnected-(U4-DSR-Pad27)") (class "Default")
      (node (ref "U4") (pin "27") (pinfunction "DSR_27") (pintype "passive+no_connect"))
    )
    (net (code "67") (name "unconnected-(U4-DTR-Pad28)") (class "Default")
      (node (ref "U4") (pin "28") (pinfunction "DTR_28") (pintype "passive+no_connect"))
    )
    (net (code "68") (name "unconnected-(U4-NC-Pad10)") (class "Default")
      (node (ref "U4") (pin "10") (pinfunction "NC_10") (pintype "passive+no_connect"))
    )
    (net (code "69") (name "unconnected-(U4-NC-Pad13)") (class "Default")
      (node (ref "U4") (pin "13") (pinfunction "NC_13") (pintype "passive+no_connect"))
    )
    (net (code "70") (name "unconnected-(U4-NC-Pad14)") (class "Default")
      (node (ref "U4") (pin "14") (pinfunction "NC_14") (pintype "passive+no_connect"))
    )
    (net (code "71") (name "unconnected-(U4-NC-Pad16)") (class "Default")
      (node (ref "U4") (pin "16") (pinfunction "NC_16") (pintype "passive+no_connect"))
    )
    (net (code "72") (name "unconnected-(U4-NC-Pad17)") (class "Default")
      (node (ref "U4") (pin "17") (pinfunction "NC_17") (pintype "passive+no_connect"))
    )
    (net (code "73") (name "unconnected-(U4-NC-Pad18)") (class "Default")
      (node (ref "U4") (pin "18") (pinfunction "NC_18") (pintype "passive+no_connect"))
    )
    (net (code "74") (name "unconnected-(U4-NC-Pad19)") (class "Default")
      (node (ref "U4") (pin "19") (pinfunction "NC_19") (pintype "passive+no_connect"))
    )
    (net (code "75") (name "unconnected-(U4-NC-Pad20)") (class "Default")
      (node (ref "U4") (pin "20") (pinfunction "NC_20") (pintype "passive+no_connect"))
    )
    (net (code "76") (name "unconnected-(U4-NC-Pad21)") (class "Default")
      (node (ref "U4") (pin "21") (pinfunction "NC_21") (pintype "passive+no_connect"))
    )
    (net (code "77") (name "unconnected-(U4-NC-Pad22)") (class "Default")
      (node (ref "U4") (pin "22") (pinfunction "NC_22") (pintype "passive+no_connect"))
    )
    (net (code "78") (name "unconnected-(U4-RI-Pad2)") (class "Default")
      (node (ref "U4") (pin "2") (pinfunction "RI_2") (pintype "passive+no_connect"))
    )
    (net (code "79") (name "unconnected-(U4-RTS-Pad24)") (class "Default")
      (node (ref "U4") (pin "24") (pinfunction "RTS_24") (pintype "passive+no_connect"))
    )
    (net (code "80") (name "unconnected-(U4-SUSPEND-Pad12)") (class "Default")
      (node (ref "U4") (pin "12") (pinfunction "SUSPEND_12") (pintype "passive+no_connect"))
    )
    (net (code "81") (name "unconnected-(U4-SUSPEND{slash}-Pad11)") (class "Default")
      (node (ref "U4") (pin "11") (pinfunction "SUSPEND/_11") (pintype "passive+no_connect"))
    )
  )
)
